# button_arduino.net
KiCad netlist of a schematic drawn in EAGLE
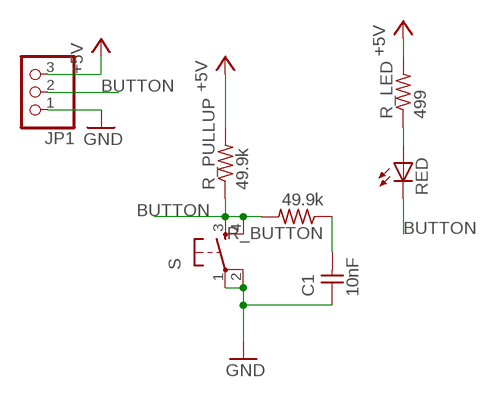
[diagram p0: schematic, sheet 1]

(export (version "E")
  (design (tool "Eeschema 10.0.6"))
  (components
    (comp (ref "C1")
      (value "10nF")
      (footprint "eagle-import:C1206FAB")
      (libsource (lib "eagle-import") (part "CAP-UNPOLARIZEDFAB"))
    )
    (comp (ref "JP1")
      (value "PINHD-1X3")
      (footprint "eagle-import:1X03")
      (libsource (lib "eagle-import") (part "PINHD-1X3"))
    )
    (comp (ref "RED")
      (value "LEDFAB1206")
      (footprint "eagle-import:LED1206FAB")
      (libsource (lib "eagle-import") (part "LEDFAB1206"))
    )
    (comp (ref "R_BUTTON")
      (value "49.9k")
      (footprint "eagle-import:R1206FAB")
      (libsource (lib "eagle-import") (part "RES-US1206FAB"))
    )
    (comp (ref "R_LED")
      (value "499")
      (footprint "eagle-import:R1206FAB")
      (libsource (lib "eagle-import") (part "RES-US1206FAB"))
    )
    (comp (ref "R_PULLUP")
      (value "49.9k")
      (footprint "eagle-import:R1206FAB")
      (libsource (lib "eagle-import") (part "RES-US1206FAB"))
    )
    (comp (ref "S")
      (value "6MM_SWITCH6MM_SWITCH")
      (footprint "eagle-import:6MM_SWITCH")
      (libsource (lib "eagle-import") (part "6MM_SWITCH6MM_SWITCH"))
    )
  )
  (nets
    (net (code "1") (name "+5V") (class "Default")
      (node (ref "JP1") (pin "3") (pinfunction "3_3") (pintype "passive"))
      (node (ref "R_LED") (pin "2") (pinfunction "2_2") (pintype "passive"))
      (node (ref "R_PULLUP") (pin "2") (pinfunction "2_2") (pintype "passive"))
    )
    (net (code "2") (name "/BUTTON") (class "Default")
      (node (ref "JP1") (pin "2") (pinfunction "2_2") (pintype "passive"))
      (node (ref "RED") (pin "2") (pinfunction "C_2") (pintype "passive"))
      (node (ref "R_BUTTON") (pin "2") (pinfunction "2_2") (pintype "passive"))
      (node (ref "R_PULLUP") (pin "1") (pinfunction "1_1") (pintype "passive"))
      (node (ref "S") (pin "3") (pinfunction "S_3") (pintype "passive"))
      (node (ref "S") (pin "4") (pinfunction "S1_4") (pintype "passive"))
    )
    (net (code "3") (name "GND") (class "Default")
      (node (ref "C1") (pin "1") (pinfunction "1_1") (pintype "passive"))
      (node (ref "JP1") (pin "1") (pinfunction "1_1") (pintype "passive"))
      (node (ref "S") (pin "1") (pinfunction "P_1") (pintype "passive"))
      (node (ref "S") (pin "2") (pinfunction "P1_2") (pintype "passive"))
    )
    (net (code "4") (name "Net-(C1-Pad2)") (class "Default")
      (node (ref "C1") (pin "2") (pinfunction "2_2") (pintype "passive"))
      (node (ref "R_BUTTON") (pin "1") (pinfunction "1_1") (pintype "passive"))
    )
    (net (code "5") (name "Net-(RED-A)") (class "Default")
      (node (ref "RED") (pin "1") (pinfunction "A_1") (pintype "passive"))
      (node (ref "R_LED") (pin "1") (pinfunction "1_1") (pintype "passive"))
    )
  )
)
